# lp_rgb.net
KiCad netlist of a schematic drawn in EAGLE
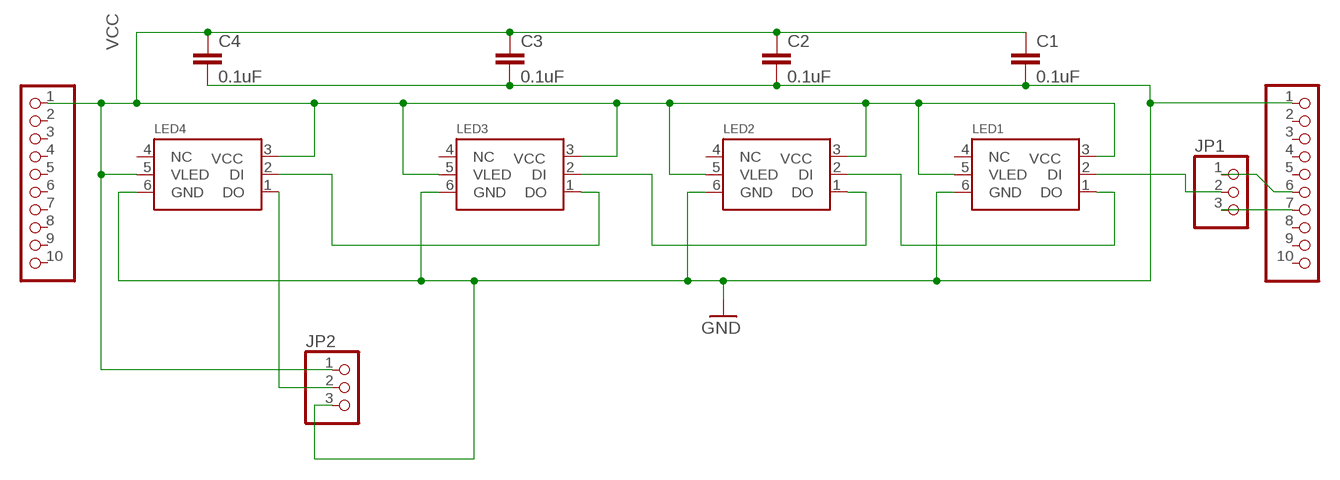
[diagram p0: schematic, sheet 1]

(export (version "E")
  (design (tool "Eeschema 10.0.6"))
  (components
    (comp (ref "C1")
      (value "0.1uF")
      (footprint "eagle-import:C0805")
      (libsource (lib "eagle-import") (part "C-EUC0805"))
    )
    (comp (ref "C2")
      (value "0.1uF")
      (footprint "eagle-import:C0805")
      (libsource (lib "eagle-import") (part "C-EUC0805"))
    )
    (comp (ref "C3")
      (value "0.1uF")
      (footprint "eagle-import:C0805")
      (libsource (lib "eagle-import") (part "C-EUC0805"))
    )
    (comp (ref "C4")
      (value "0.1uF")
      (footprint "eagle-import:C0805")
      (libsource (lib "eagle-import") (part "C-EUC0805"))
    )
    (comp (ref "J1")
      (value "J1")
      (footprint "eagle-import:1X10")
      (libsource (lib "eagle-import") (part "PINHD-1X10"))
    )
    (comp (ref "J2")
      (value "J2")
      (footprint "eagle-import:1X10")
      (libsource (lib "eagle-import") (part "PINHD-1X10"))
    )
    (comp (ref "JP1")
      (value "PINHD-1X3")
      (footprint "eagle-import:1X03")
      (libsource (lib "eagle-import") (part "PINHD-1X3"))
    )
    (comp (ref "JP2")
      (value "PINHD-1X3")
      (footprint "eagle-import:1X03")
      (libsource (lib "eagle-import") (part "PINHD-1X3"))
    )
    (comp (ref "LED1")
      (value "5050WS2811W")
      (footprint "eagle-import:RGBLED5050W")
      (libsource (lib "eagle-import") (part "5050WS2811W"))
    )
    (comp (ref "LED2")
      (value "5050WS2811W")
      (footprint "eagle-import:RGBLED5050W")
      (libsource (lib "eagle-import") (part "5050WS2811W"))
    )
    (comp (ref "LED3")
      (value "5050WS2811W")
      (footprint "eagle-import:RGBLED5050W")
      (libsource (lib "eagle-import") (part "5050WS2811W"))
    )
    (comp (ref "LED4")
      (value "5050WS2811W")
      (footprint "eagle-import:RGBLED5050W")
      (libsource (lib "eagle-import") (part "5050WS2811W"))
    )
  )
  (nets
    (net (code "1") (name "/VCC") (class "Default")
      (node (ref "C1") (pin "1") (pinfunction "1_1") (pintype "passive"))
      (node (ref "C2") (pin "1") (pinfunction "1_1") (pintype "passive"))
      (node (ref "C3") (pin "1") (pinfunction "1_1") (pintype "passive"))
      (node (ref "C4") (pin "1") (pinfunction "1_1") (pintype "passive"))
      (node (ref "J1") (pin "1") (pinfunction "1_1") (pintype "passive"))
      (node (ref "JP2") (pin "1") (pinfunction "1_1") (pintype "passive"))
      (node (ref "LED1") (pin "3") (pinfunction "VCC_3") (pintype "bidirectional"))
      (node (ref "LED1") (pin "5") (pinfunction "VLED_5") (pintype "bidirectional"))
      (node (ref "LED2") (pin "3") (pinfunction "VCC_3") (pintype "bidirectional"))
      (node (ref "LED2") (pin "5") (pinfunction "VLED_5") (pintype "bidirectional"))
      (node (ref "LED3") (pin "3") (pinfunction "VCC_3") (pintype "bidirectional"))
      (node (ref "LED3") (pin "5") (pinfunction "VLED_5") (pintype "bidirectional"))
      (node (ref "LED4") (pin "3") (pinfunction "VCC_3") (pintype "bidirectional"))
      (node (ref "LED4") (pin "5") (pinfunction "VLED_5") (pintype "bidirectional"))
    )
    (net (code "2") (name "GND") (class "Default")
      (node (ref "C1") (pin "2") (pinfunction "2_2") (pintype "passive"))
      (node (ref "C2") (pin "2") (pinfunction "2_2") (pintype "passive"))
      (node (ref "C3") (pin "2") (pinfunction "2_2") (pintype "passive"))
      (node (ref "C4") (pin "2") (pinfunction "2_2") (pintype "passive"))
      (node (ref "J2") (pin "1") (pinfunction "1_1") (pintype "passive"))
      (node (ref "JP2") (pin "3") (pinfunction "3_3") (pintype "passive"))
      (node (ref "LED1") (pin "6") (pinfunction "GND_6") (pintype "bidirectional"))
      (node (ref "LED2") (pin "6") (pinfunction "GND_6") (pintype "bidirectional"))
      (node (ref "LED3") (pin "6") (pinfunction "GND_6") (pintype "bidirectional"))
      (node (ref "LED4") (pin "6") (pinfunction "GND_6") (pintype "bidirectional"))
    )
    (net (code "3") (name "Net-(J2-Pad6)") (class "Default")
      (node (ref "J2") (pin "6") (pinfunction "6_6") (pintype "passive"))
      (node (ref "JP1") (pin "1") (pinfunction "1_1") (pintype "passive"))
    )
    (net (code "4") (name "Net-(J2-Pad7)") (class "Default")
      (node (ref "J2") (pin "7") (pinfunction "7_7") (pintype "passive"))
      (node (ref "JP1") (pin "3") (pinfunction "3_3") (pintype "passive"))
    )
    (net (code "5") (name "Net-(LED1-DI)") (class "Default")
      (node (ref "JP1") (pin "2") (pinfunction "2_2") (pintype "passive"))
      (node (ref "LED1") (pin "2") (pinfunction "DI_2") (pintype "bidirectional"))
    )
    (net (code "6") (name "Net-(LED1-DO)") (class "Default")
      (node (ref "LED1") (pin "1") (pinfunction "DO_1") (pintype "bidirectional"))
      (node (ref "LED2") (pin "2") (pinfunction "DI_2") (pintype "bidirectional"))
    )
    (net (code "7") (name "Net-(LED2-DO)") (class "Default")
      (node (ref "LED2") (pin "1") (pinfunction "DO_1") (pintype "bidirectional"))
      (node (ref "LED3") (pin "2") (pinfunction "DI_2") (pintype "bidirectional"))
    )
    (net (code "8") (name "Net-(LED3-DO)") (class "Default")
      (node (ref "LED3") (pin "1") (pinfunction "DO_1") (pintype "bidirectional"))
      (node (ref "LED4") (pin "2") (pinfunction "DI_2") (pintype "bidirectional"))
    )
    (net (code "9") (name "Net-(LED4-DO)") (class "Default")
      (node (ref "JP2") (pin "2") (pinfunction "2_2") (pintype "passive"))
      (node (ref "LED4") (pin "1") (pinfunction "DO_1") (pintype "bidirectional"))
    )
    (net (code "10") (name "unconnected-(J1-Pad2)") (class "Default")
      (node (ref "J1") (pin "2") (pinfunction "2_2") (pintype "passive"))
    )
    (net (code "11") (name "unconnected-(J1-Pad3)") (class "Default")
      (node (ref "J1") (pin "3") (pinfunction "3_3") (pintype "passive"))
    )
    (net (code "12") (name "unconnected-(J1-Pad4)") (class "Default")
      (node (ref "J1") (pin "4") (pinfunction "4_4") (pintype "passive"))
    )
    (net (code "13") (name "unconnected-(J1-Pad5)") (class "Default")
      (node (ref "J1") (pin "5") (pinfunction "5_5") (pintype "passive"))
    )
    (net (code "14") (name "unconnected-(J1-Pad6)") (class "Default")
      (node (ref "J1") (pin "6") (pinfunction "6_6") (pintype "passive"))
    )
    (net (code "15") (name "unconnected-(J1-Pad7)") (class "Default")
      (node (ref "J1") (pin "7") (pinfunction "7_7") (pintype "passive"))
    )
    (net (code "16") (name "unconnected-(J1-Pad8)") (class "Default")
      (node (ref "J1") (pin "8") (pinfunction "8_8") (pintype "passive"))
    )
    (net (code "17") (name "unconnected-(J1-Pad9)") (class "Default")
      (node (ref "J1") (pin "9") (pinfunction "9_9") (pintype "passive"))
    )
    (net (code "18") (name "unconnected-(J1-Pad10)") (class "Default")
      (node (ref "J1") (pin "10") (pinfunction "10_10") (pintype "passive"))
    )
    (net (code "19") (name "unconnected-(J2-Pad2)") (class "Default")
      (node (ref "J2") (pin "2") (pinfunction "2_2") (pintype "passive"))
    )
    (net (code "20") (name "unconnected-(J2-Pad3)") (class "Default")
      (node (ref "J2") (pin "3") (pinfunction "3_3") (pintype "passive"))
    )
    (net (code "21") (name "unconnected-(J2-Pad4)") (class "Default")
      (node (ref "J2") (pin "4") (pinfunction "4_4") (pintype "passive"))
    )
    (net (code "22") (name "unconnected-(J2-Pad5)") (class "Default")
      (node (ref "J2") (pin "5") (pinfunction "5_5") (pintype "passive"))
    )
    (net (code "23") (name "unconnected-(J2-Pad8)") (class "Default")
      (node (ref "J2") (pin "8") (pinfunction "8_8") (pintype "passive"))
    )
    (net (code "24") (name "unconnected-(J2-Pad9)") (class "Default")
      (node (ref "J2") (pin "9") (pinfunction "9_9") (pintype "passive"))
    )
    (net (code "25") (name "unconnected-(J2-Pad10)") (class "Default")
      (node (ref "J2") (pin "10") (pinfunction "10_10") (pintype "passive"))
    )
    (net (code "26") (name "unconnected-(LED1-NC-Pad4)") (class "Default")
      (node (ref "LED1") (pin "4") (pinfunction "NC_4") (pintype "bidirectional"))
    )
    (net (code "27") (name "unconnected-(LED2-NC-Pad4)") (class "Default")
      (node (ref "LED2") (pin "4") (pinfunction "NC_4") (pintype "bidirectional"))
    )
    (net (code "28") (name "unconnected-(LED3-NC-Pad4)") (class "Default")
      (node (ref "LED3") (pin "4") (pinfunction "NC_4") (pintype "bidirectional"))
    )
    (net (code "29") (name "unconnected-(LED4-NC-Pad4)") (class "Default")
      (node (ref "LED4") (pin "4") (pinfunction "NC_4") (pintype "bidirectional"))
    )
  )
)
